# 09_MRAM_RTC_WDT.net
KiCad netlist of a schematic drawn in Altium Designer
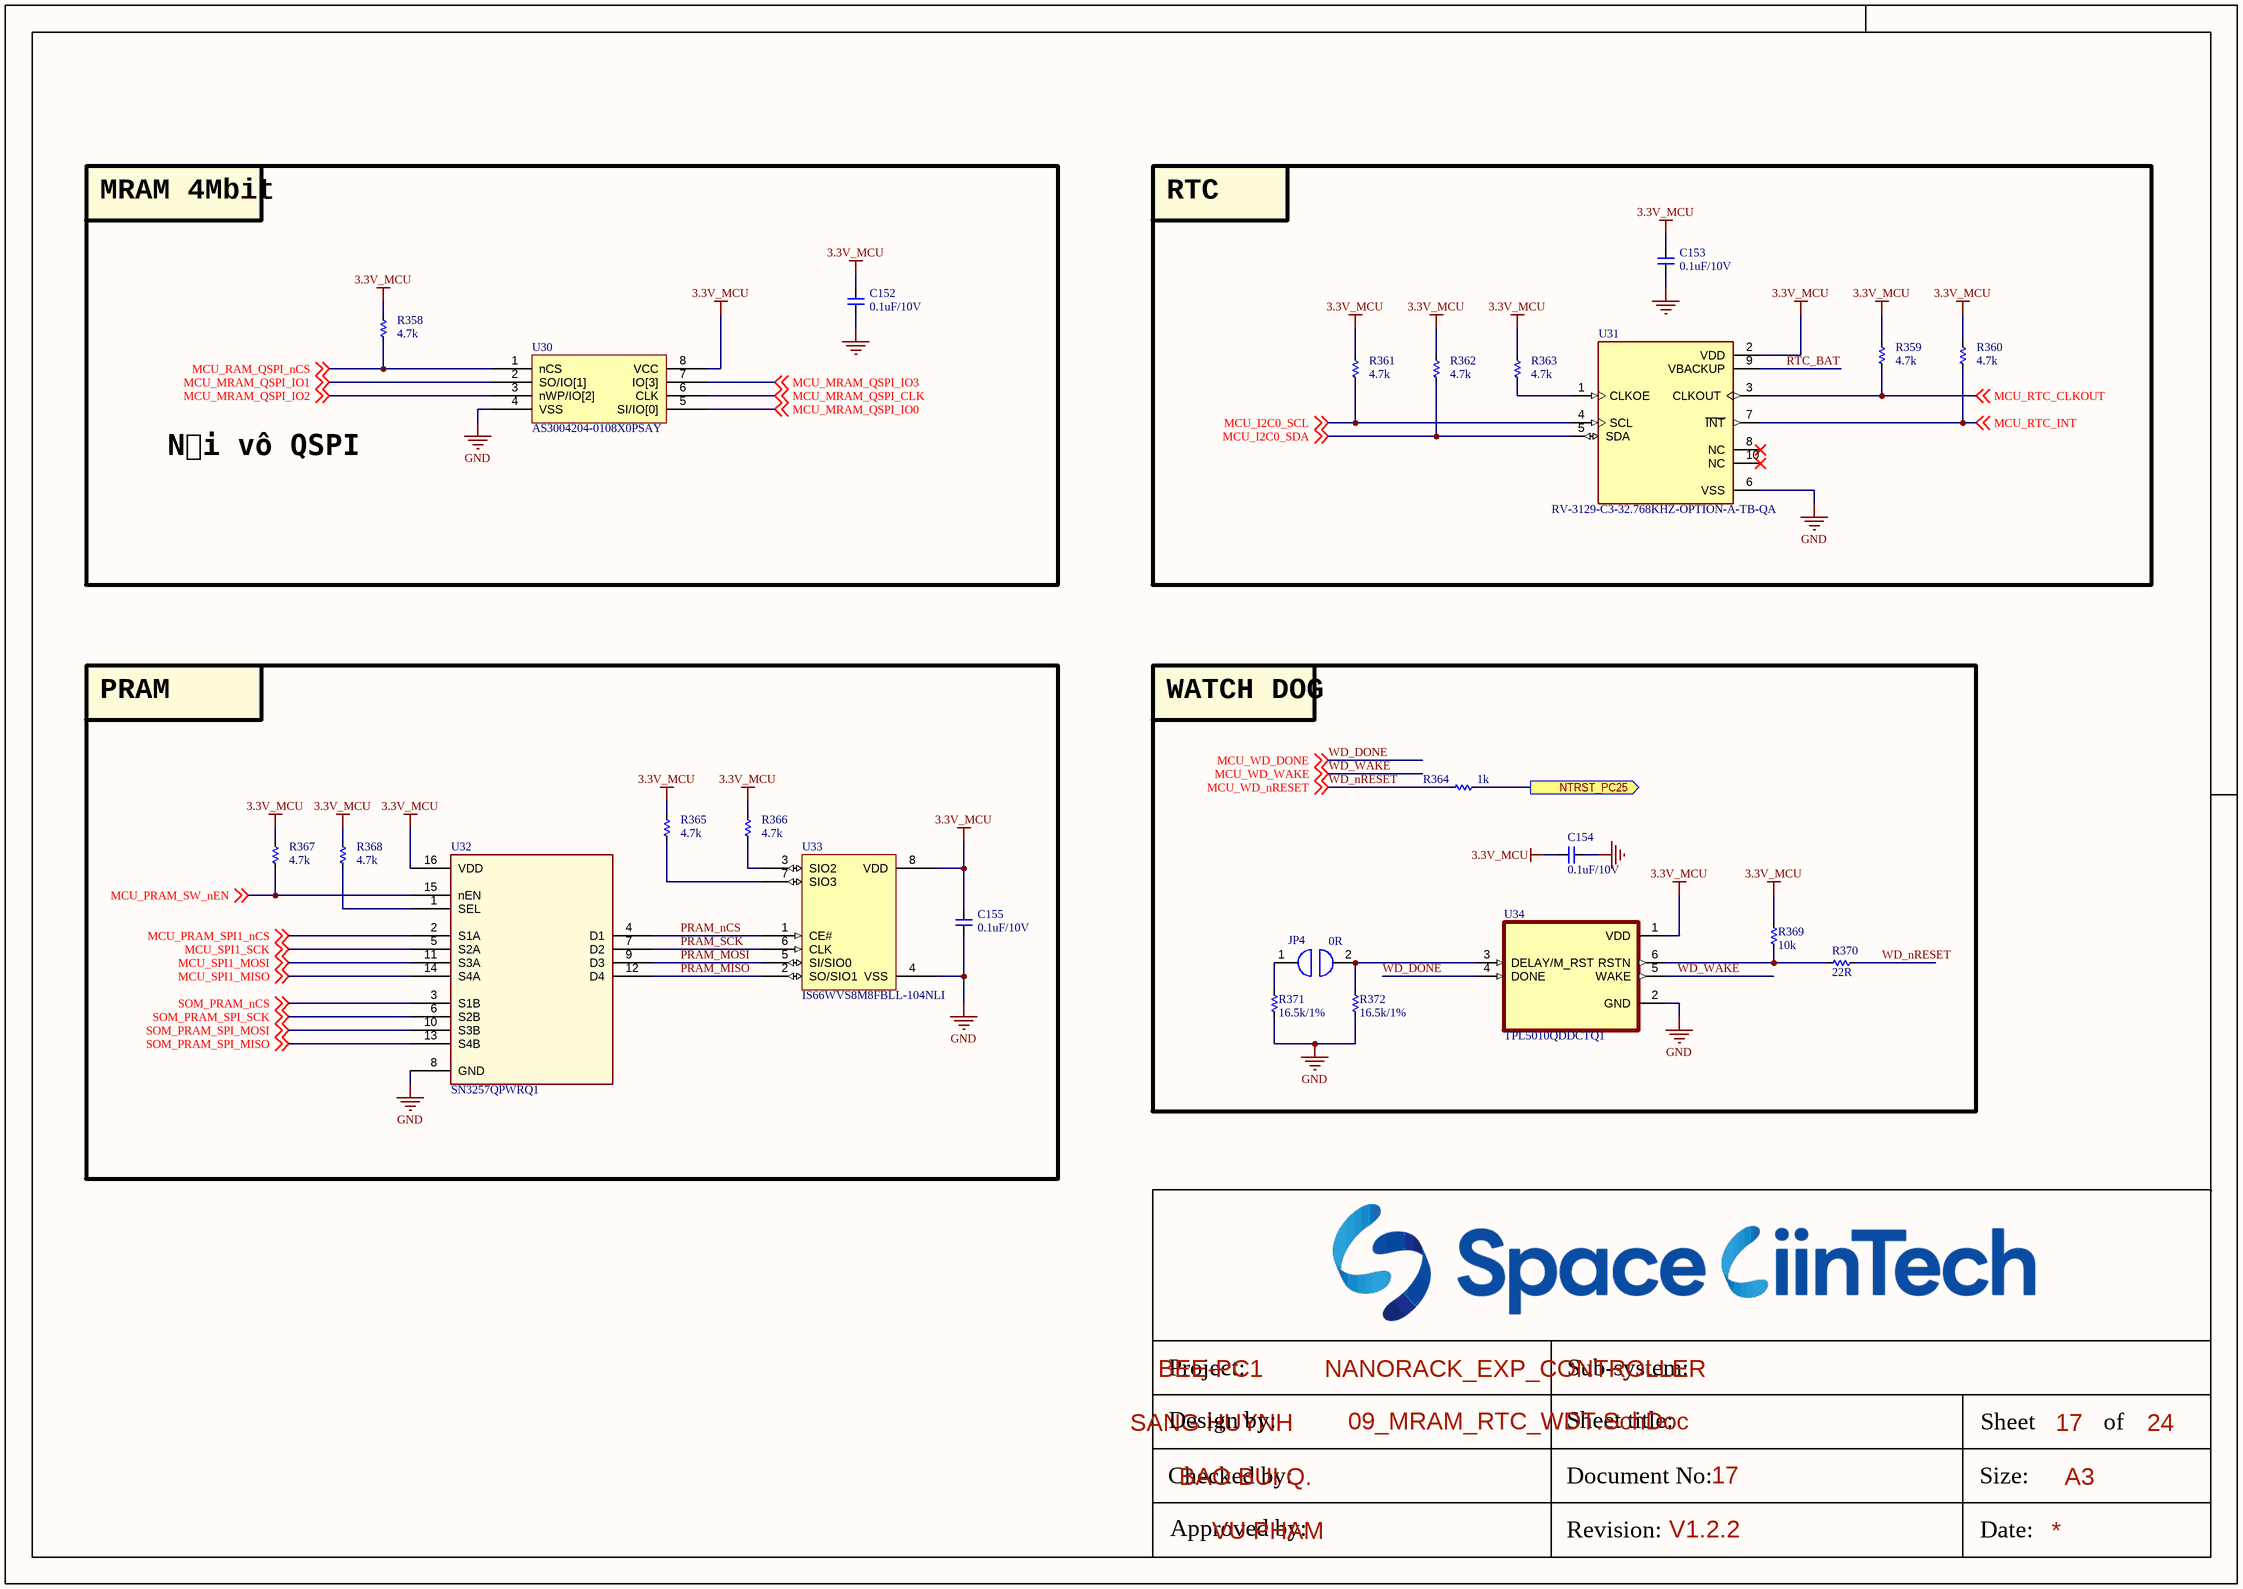
[diagram p0: 09_MRAM_RTC_WDT.SchDoc]

(export (version "E")
  (design (tool "Eeschema 10.0.6"))
  (components
    (comp (ref "C152")
      (value "0.1uF/10V")
      (footprint "CAP_C_1005X60")
      (description "CAP CHIP")
      (libsource (lib "LABLIB") (part "_CAP_C_2"))
    )
    (comp (ref "C153")
      (value "0.1uF/10V")
      (footprint "CAP_C_1005X60")
      (description "CAP CHIP")
      (libsource (lib "LABLIB") (part "_CAP_C_2"))
    )
    (comp (ref "C154")
      (value "0.1uF/10V")
      (footprint "CAP_C_1005X60")
      (description "CAP CHIP")
      (libsource (lib "LABLIB") (part "_CAP_C_2"))
    )
    (comp (ref "C155")
      (value "0.1uF/10V")
      (footprint "CAP_C_1005X60")
      (description "CAP CHIP")
      (libsource (lib "LABLIB") (part "_CAP_C_2"))
    )
    (comp (ref "JP4") (value "0R") (footprint "RES_C_1608X60") (libsource (lib "EXP_V1") (part "JUMPER")))
    (comp (ref "R358")
      (value "4.7k")
      (footprint "RES_C_1005X40")
      (description "RES")
      (libsource (lib "LABLIB") (part "_RES_B_2"))
    )
    (comp (ref "R359")
      (value "4.7k")
      (footprint "RES_C_1005X40")
      (description "RES")
      (libsource (lib "LABLIB") (part "_RES_B_2"))
    )
    (comp (ref "R360")
      (value "4.7k")
      (footprint "RES_C_1005X40")
      (description "RES")
      (libsource (lib "LABLIB") (part "_RES_B_2"))
    )
    (comp (ref "R361")
      (value "4.7k")
      (footprint "RES_C_1005X40")
      (description "RES")
      (libsource (lib "LABLIB") (part "_RES_B_2"))
    )
    (comp (ref "R362")
      (value "4.7k")
      (footprint "RES_C_1005X40")
      (description "RES")
      (libsource (lib "LABLIB") (part "_RES_B_2"))
    )
    (comp (ref "R363")
      (value "4.7k")
      (footprint "RES_C_1005X40")
      (description "RES")
      (libsource (lib "LABLIB") (part "_RES_B_2"))
    )
    (comp (ref "R364")
      (value "1k")
      (footprint "RES_C_1005X40")
      (description "RES")
      (libsource (lib "LABLIB") (part "_RES_B_2"))
    )
    (comp (ref "R365")
      (value "4.7k")
      (footprint "RES_C_1005X40")
      (description "RES")
      (libsource (lib "LABLIB") (part "_RES_B_2"))
    )
    (comp (ref "R366")
      (value "4.7k")
      (footprint "RES_C_1005X40")
      (description "RES")
      (libsource (lib "LABLIB") (part "_RES_B_2"))
    )
    (comp (ref "R367")
      (value "4.7k")
      (footprint "RES_C_1005X40")
      (description "RES")
      (libsource (lib "LABLIB") (part "_RES_B_2"))
    )
    (comp (ref "R368")
      (value "4.7k")
      (footprint "RES_C_1005X40")
      (description "RES")
      (libsource (lib "LABLIB") (part "_RES_B_2"))
    )
    (comp (ref "R369")
      (value "10k")
      (footprint "RES_C_1005X40")
      (description "RES")
      (libsource (lib "LABLIB") (part "_RES_B_2"))
    )
    (comp (ref "R370")
      (value "22R")
      (footprint "RES_C_1005X40")
      (description "RES")
      (libsource (lib "LABLIB") (part "_RES_B_2"))
    )
    (comp (ref "R371")
      (value "16.5k/1%")
      (footprint "RES_C_1005X40")
      (description "RES")
      (libsource (lib "LABLIB") (part "_RES_B_2"))
    )
    (comp (ref "R372")
      (value "16.5k/1%")
      (footprint "RES_C_1005X40")
      (description "RES")
      (libsource (lib "LABLIB") (part "_RES_B_2"))
    )
    (comp (ref "U30")
      (value "AS3004204-0108X0PSAY")
      (footprint "SOIC127P790X216-8")
      (libsource (lib "LABLIB") (part "IC_RAM_AS3004204-0108X0PSAY"))
    )
    (comp (ref "U31")
      (value "RV-3129-C3-32.768KHZ-OPTION-A-TB-QA")
      (footprint "IC_RV-3129-C3_32.768KHZ_OPTION_A_TB_QA")
      (description "Real-Time Clock Module, Temperature compensated, in 2.5 x 3.7 mm package")
      (fields (field (name "MF") "Micro Crystal") (field (name "MP") "RV-3129-C3 32.768KHZ OPTION A TB QA"))
      (libsource (lib "RV-3129-C3_32.768KHZ_OPTION_A_TB_QA") (part "RV-3129-C3_32.768KHZ_OPTION_A_TB_QA"))
    )
    (comp (ref "U32")
      (value "SN3257QPWRQ1")
      (footprint "SOIC_PRQ1_TEX")
      (fields (field (name "COPYRIGHT") "Copyright (C) 2025 Ultra Librarian. All rights reserved."))
      (libsource (lib "LABLIB") (part "IC_SW_SPI_SN3257QPWRQ1"))
    )
    (comp (ref "U33")
      (value "IS66WVS8M8FBLL-104NLI")
      (footprint "SOIC8_150MIL_N_ISI")
      (description "No Description Available")
      (fields
        (field (name "MANUFACTURER_PART_NUMBER") "IS66WVS4M8BLL-104NLI")
        (field (name "COPYRIGHT") "Copyright (C) 2025 Ultra Librarian. All rights reserved.")
      )
      (libsource (lib "LABLIB") (part "IS66WVS4M8BLL-104NLI"))
    )
    (comp (ref "U34")
      (value "TPL5010QDDCTQ1")
      (footprint "SOT95P280X145-6N")
      (libsource (lib "TPL5010QDDCTQ1") (part "TPL5010QDDCTQ1"))
    )
  )
  (nets
    (net (code "1") (name "/NTRST_PC25") (class "Default")
      (node (ref "R364") (pin "1") (pinfunction "1_1") (pintype "passive"))
    )
    (net (code "2") (name "/PRAM_MISO") (class "Default")
      (node (ref "U32") (pin "12") (pinfunction "D4_12") (pintype "passive"))
      (node (ref "U33") (pin "2") (pinfunction "SO/SIO1_2") (pintype "bidirectional"))
    )
    (net (code "3") (name "/PRAM_MOSI") (class "Default")
      (node (ref "U32") (pin "9") (pinfunction "D3_9") (pintype "passive"))
      (node (ref "U33") (pin "5") (pinfunction "SI/SIO0_5") (pintype "bidirectional"))
    )
    (net (code "4") (name "/PRAM_SCK") (class "Default")
      (node (ref "U32") (pin "7") (pinfunction "D2_7") (pintype "passive"))
      (node (ref "U33") (pin "6") (pinfunction "CLK_6") (pintype "input"))
    )
    (net (code "5") (name "/PRAM_nCS") (class "Default")
      (node (ref "U32") (pin "4") (pinfunction "D1_4") (pintype "passive"))
      (node (ref "U33") (pin "1") (pinfunction "CE#_1") (pintype "input"))
    )
    (net (code "6") (name "/RTC_BAT") (class "Default")
      (node (ref "U31") (pin "9") (pinfunction "VBACKUP_9") (pintype "power_in"))
    )
    (net (code "7") (name "3.3V_MCU") (class "Default")
      (node (ref "C152") (pin "2") (pinfunction "2_2") (pintype "passive"))
      (node (ref "C153") (pin "2") (pinfunction "2_2") (pintype "passive"))
      (node (ref "C154") (pin "2") (pinfunction "2_2") (pintype "passive"))
      (node (ref "C155") (pin "1") (pinfunction "1_1") (pintype "passive"))
      (node (ref "R358") (pin "2") (pinfunction "2_2") (pintype "passive"))
      (node (ref "R359") (pin "2") (pinfunction "2_2") (pintype "passive"))
      (node (ref "R360") (pin "2") (pinfunction "2_2") (pintype "passive"))
      (node (ref "R361") (pin "2") (pinfunction "2_2") (pintype "passive"))
      (node (ref "R362") (pin "2") (pinfunction "2_2") (pintype "passive"))
      (node (ref "R363") (pin "1") (pinfunction "1_1") (pintype "passive"))
      (node (ref "R365") (pin "2") (pinfunction "2_2") (pintype "passive"))
      (node (ref "R366") (pin "2") (pinfunction "2_2") (pintype "passive"))
      (node (ref "R367") (pin "2") (pinfunction "2_2") (pintype "passive"))
      (node (ref "R368") (pin "2") (pinfunction "2_2") (pintype "passive"))
      (node (ref "R369") (pin "2") (pinfunction "2_2") (pintype "passive"))
      (node (ref "U30") (pin "8") (pinfunction "VCC_8") (pintype "passive"))
      (node (ref "U31") (pin "2") (pinfunction "VDD_2") (pintype "power_in"))
      (node (ref "U32") (pin "16") (pinfunction "VDD_16") (pintype "passive"))
      (node (ref "U33") (pin "8") (pinfunction "VDD_8") (pintype "power_in"))
      (node (ref "U34") (pin "1") (pinfunction "VDD_1") (pintype "power_in"))
    )
    (net (code "8") (name "GND") (class "Default")
      (node (ref "C152") (pin "1") (pinfunction "1_1") (pintype "passive"))
      (node (ref "C153") (pin "1") (pinfunction "1_1") (pintype "passive"))
      (node (ref "C154") (pin "1") (pinfunction "1_1") (pintype "passive"))
      (node (ref "C155") (pin "2") (pinfunction "2_2") (pintype "passive"))
      (node (ref "R371") (pin "1") (pinfunction "1_1") (pintype "passive"))
      (node (ref "R372") (pin "1") (pinfunction "1_1") (pintype "passive"))
      (node (ref "U30") (pin "4") (pinfunction "VSS_4") (pintype "passive"))
      (node (ref "U31") (pin "6") (pinfunction "VSS_6") (pintype "power_in"))
      (node (ref "U32") (pin "8") (pinfunction "GND_8") (pintype "passive"))
      (node (ref "U33") (pin "4") (pinfunction "VSS_4") (pintype "power_in"))
      (node (ref "U34") (pin "2") (pinfunction "GND_2") (pintype "power_in"))
    )
    (net (code "9") (name "MCU_I2C0_SCL") (class "Default")
      (node (ref "R361") (pin "1") (pinfunction "1_1") (pintype "passive"))
      (node (ref "U31") (pin "4") (pinfunction "SCL_4") (pintype "input"))
    )
    (net (code "10") (name "MCU_I2C0_SDA") (class "Default")
      (node (ref "R362") (pin "1") (pinfunction "1_1") (pintype "passive"))
      (node (ref "U31") (pin "5") (pinfunction "SDA_5") (pintype "bidirectional"))
    )
    (net (code "11") (name "MCU_MRAM_QSPI_CLK") (class "Default")
      (node (ref "U30") (pin "6") (pinfunction "CLK_6") (pintype "passive"))
    )
    (net (code "12") (name "MCU_MRAM_QSPI_IO0") (class "Default")
      (node (ref "U30") (pin "5") (pinfunction "SI/IO[0]_5") (pintype "passive"))
    )
    (net (code "13") (name "MCU_MRAM_QSPI_IO1") (class "Default")
      (node (ref "U30") (pin "2") (pinfunction "SO/IO[1]_2") (pintype "passive"))
    )
    (net (code "14") (name "MCU_MRAM_QSPI_IO2") (class "Default")
      (node (ref "U30") (pin "3") (pinfunction "nWP/IO[2]_3") (pintype "passive"))
    )
    (net (code "15") (name "MCU_MRAM_QSPI_IO3") (class "Default")
      (node (ref "U30") (pin "7") (pinfunction "IO[3]_7") (pintype "passive"))
    )
    (net (code "16") (name "MCU_PRAM_SPI1_nCS") (class "Default")
      (node (ref "U32") (pin "2") (pinfunction "S1A_2") (pintype "passive"))
    )
    (net (code "17") (name "MCU_PRAM_SW_nEN") (class "Default")
      (node (ref "R367") (pin "1") (pinfunction "1_1") (pintype "passive"))
      (node (ref "U32") (pin "15") (pinfunction "nEN_15") (pintype "passive"))
    )
    (net (code "18") (name "MCU_RAM_QSPI_nCS") (class "Default")
      (node (ref "R358") (pin "1") (pinfunction "1_1") (pintype "passive"))
      (node (ref "U30") (pin "1") (pinfunction "nCS_1") (pintype "passive"))
    )
    (net (code "19") (name "MCU_RTC_CLKOUT") (class "Default")
      (node (ref "R359") (pin "1") (pinfunction "1_1") (pintype "passive"))
      (node (ref "U31") (pin "3") (pinfunction "CLKOUT_3") (pintype "output"))
    )
    (net (code "20") (name "MCU_RTC_INT") (class "Default")
      (node (ref "R360") (pin "1") (pinfunction "1_1") (pintype "passive"))
      (node (ref "U31") (pin "7") (pinfunction "~{INT}_7") (pintype "output"))
    )
    (net (code "21") (name "MCU_SPI1_MISO") (class "Default")
      (node (ref "U32") (pin "14") (pinfunction "S4A_14") (pintype "passive"))
    )
    (net (code "22") (name "MCU_SPI1_MOSI") (class "Default")
      (node (ref "U32") (pin "11") (pinfunction "S3A_11") (pintype "passive"))
    )
    (net (code "23") (name "MCU_SPI1_SCK") (class "Default")
      (node (ref "U32") (pin "5") (pinfunction "S2A_5") (pintype "passive"))
    )
    (net (code "24") (name "MCU_WD_DONE") (class "Default")
      (node (ref "U34") (pin "4") (pinfunction "DONE_4") (pintype "input"))
    )
    (net (code "25") (name "MCU_WD_WAKE") (class "Default")
      (node (ref "U34") (pin "5") (pinfunction "WAKE_5") (pintype "output"))
    )
    (net (code "26") (name "MCU_WD_nRESET") (class "Default")
      (node (ref "R364") (pin "2") (pinfunction "2_2") (pintype "passive"))
      (node (ref "R370") (pin "1") (pinfunction "1_1") (pintype "passive"))
    )
    (net (code "27") (name "Net-(JP4-Pad1)") (class "Default")
      (node (ref "JP4") (pin "1") (pinfunction "1_1") (pintype "passive"))
      (node (ref "R371") (pin "2") (pinfunction "2_2") (pintype "passive"))
    )
    (net (code "28") (name "Net-(U31-CLKOE)") (class "Default")
      (node (ref "R363") (pin "2") (pinfunction "2_2") (pintype "passive"))
      (node (ref "U31") (pin "1") (pinfunction "CLKOE_1") (pintype "input"))
    )
    (net (code "29") (name "Net-(U32-SEL)") (class "Default")
      (node (ref "R368") (pin "1") (pinfunction "1_1") (pintype "passive"))
      (node (ref "U32") (pin "1") (pinfunction "SEL_1") (pintype "passive"))
    )
    (net (code "30") (name "Net-(U33-SIO2)") (class "Default")
      (node (ref "R366") (pin "1") (pinfunction "1_1") (pintype "passive"))
      (node (ref "U33") (pin "3") (pinfunction "SIO2_3") (pintype "bidirectional"))
    )
    (net (code "31") (name "Net-(U33-SIO3)") (class "Default")
      (node (ref "R365") (pin "1") (pinfunction "1_1") (pintype "passive"))
      (node (ref "U33") (pin "7") (pinfunction "SIO3_7") (pintype "bidirectional"))
    )
    (net (code "32") (name "Net-(U34-DELAY{slash}M_RST)") (class "Default")
      (node (ref "JP4") (pin "2") (pinfunction "2_2") (pintype "passive"))
      (node (ref "R372") (pin "2") (pinfunction "2_2") (pintype "passive"))
      (node (ref "U34") (pin "3") (pinfunction "DELAY/M_RST_3") (pintype "input"))
    )
    (net (code "33") (name "Net-(U34-RSTN)") (class "Default")
      (node (ref "R369") (pin "1") (pinfunction "1_1") (pintype "passive"))
      (node (ref "R370") (pin "2") (pinfunction "2_2") (pintype "passive"))
      (node (ref "U34") (pin "6") (pinfunction "RSTN_6") (pintype "output"))
    )
    (net (code "34") (name "SOM_PRAM_SPI_MISO") (class "Default")
      (node (ref "U32") (pin "13") (pinfunction "S4B_13") (pintype "passive"))
    )
    (net (code "35") (name "SOM_PRAM_SPI_MOSI") (class "Default")
      (node (ref "U32") (pin "10") (pinfunction "S3B_10") (pintype "passive"))
    )
    (net (code "36") (name "SOM_PRAM_SPI_SCK") (class "Default")
      (node (ref "U32") (pin "6") (pinfunction "S2B_6") (pintype "passive"))
    )
    (net (code "37") (name "SOM_PRAM_nCS") (class "Default")
      (node (ref "U32") (pin "3") (pinfunction "S1B_3") (pintype "passive"))
    )
    (net (code "38") (name "unconnected-(U31-NC-Pad8)") (class "Default")
      (node (ref "U31") (pin "8") (pinfunction "NC_8") (pintype "passive+no_connect"))
    )
    (net (code "39") (name "unconnected-(U31-NC-Pad10)") (class "Default")
      (node (ref "U31") (pin "10") (pinfunction "NC_10") (pintype "passive+no_connect"))
    )
  )
)
